# TB_Power_supply_pcb.net
KiCad netlist of a schematic drawn in Altium Designer
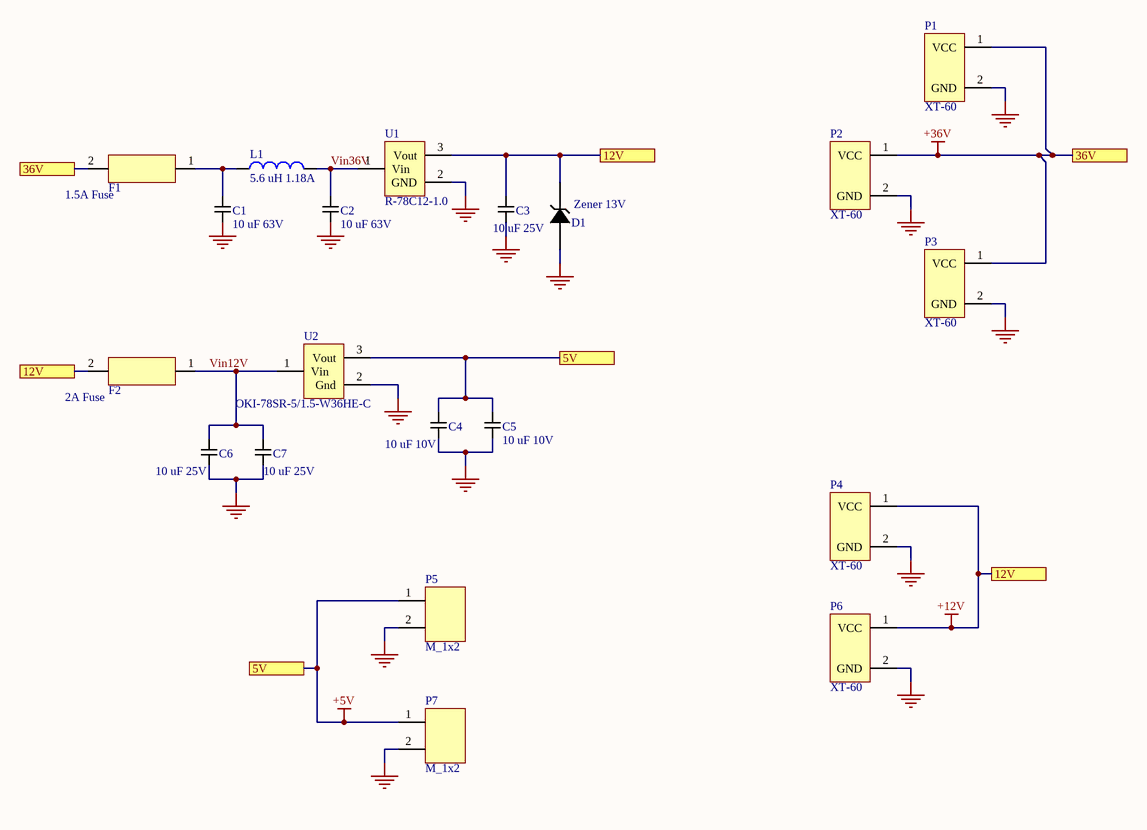
[diagram p0: TB Power supply pcb.SchDoc]

(export (version "E")
  (design (tool "Eeschema 10.0.6"))
  (components
    (comp (ref "C1")
      (value "10 uF 63V")
      (footprint "C_smd_3225")
      (fields (field (name "Comment") "SMD"))
      (libsource (lib "FF_component_lib") (part "C_SMD_3225"))
    )
    (comp (ref "C2")
      (value "10 uF 63V")
      (footprint "C_smd_3225")
      (fields (field (name "Comment") "SMD"))
      (libsource (lib "FF_component_lib") (part "C_SMD_3225"))
    )
    (comp (ref "C3")
      (value "10 uF 25V")
      (footprint "C_SMD_0805_pcb")
      (fields (field (name "Comment") "SMD"))
      (libsource (lib "FF_component_lib") (part "C_SMD_0805"))
    )
    (comp (ref "C4")
      (value "10 uF 10V")
      (footprint "C_SMD_0805_pcb")
      (fields (field (name "Comment") "SMD"))
      (libsource (lib "FF_component_lib") (part "C_SMD_0805"))
    )
    (comp (ref "C5")
      (value "10 uF 10V")
      (footprint "C_SMD_0805_pcb")
      (fields (field (name "Comment") "SMD"))
      (libsource (lib "FF_component_lib") (part "C_SMD_0805"))
    )
    (comp (ref "C6")
      (value "10 uF 25V")
      (footprint "C_SMD_0805_pcb")
      (fields (field (name "Comment") "SMD"))
      (libsource (lib "FF_component_lib") (part "C_SMD_0805"))
    )
    (comp (ref "C7")
      (value "10 uF 25V")
      (footprint "C_SMD_0805_pcb")
      (fields (field (name "Comment") "SMD"))
      (libsource (lib "FF_component_lib") (part "C_SMD_0805"))
    )
    (comp (ref "D1")
      (value "Zener 13V")
      (footprint "D_ZENER_12V_smd")
      (fields (field (name "Comment") "D_ZENER_smd_13V"))
      (libsource (lib "FF_component_lib") (part "D_ZENER_smd_13V"))
    )
    (comp (ref "F1")
      (value "1.5A Fuse")
      (footprint "fuse_holder_3A")
      (description "(22.352mm x6.858mm)")
      (fields (field (name "Comment") "Fuse-holder-3A"))
      (libsource (lib "FF_component_lib") (part "Fuse-holder-3A"))
    )
    (comp (ref "F2")
      (value "2A Fuse")
      (footprint "fuse_holder_3A")
      (description "(22.352mm x6.858mm)")
      (fields (field (name "Comment") "Fuse-holder-3A"))
      (libsource (lib "FF_component_lib") (part "Fuse-holder-3A"))
    )
    (comp (ref "L1")
      (value "5.6 uH 1.18A")
      (footprint "L_1.18A_4532")
      (fields (field (name "Comment") "L_1.18A_4532"))
      (libsource (lib "FF_component_lib") (part "L_1.18A_4532"))
    )
    (comp (ref "P1") (value "XT-60") (footprint "XT-60") (libsource (lib "FF_component_lib") (part "XT-60")))
    (comp (ref "P2") (value "XT-60") (footprint "XT-60") (libsource (lib "FF_component_lib") (part "XT-60")))
    (comp (ref "P3") (value "XT-60") (footprint "XT-60") (libsource (lib "FF_component_lib") (part "XT-60")))
    (comp (ref "P4") (value "XT-60") (footprint "XT-60") (libsource (lib "FF_component_lib") (part "XT-60")))
    (comp (ref "P5")
      (value "M_1x2")
      (footprint "PIN_HEADER_M_1x2")
      (libsource (lib "FF_component_lib") (part "PIN_HEADER_M_1x2"))
    )
    (comp (ref "P6") (value "XT-60") (footprint "XT-60") (libsource (lib "FF_component_lib") (part "XT-60")))
    (comp (ref "P7")
      (value "M_1x2")
      (footprint "PIN_HEADER_M_1x2")
      (libsource (lib "FF_component_lib") (part "PIN_HEADER_M_1x2"))
    )
    (comp (ref "U1")
      (value "R-78C12-1.0")
      (footprint "R-78C12-1.0")
      (description "Wide input - 12V out buck")
      (libsource (lib "FF_component_lib") (part "R-78C12-1.0"))
    )
    (comp (ref "U2")
      (value "OKI-78SR-5/1.5-W36HE-C")
      (footprint "OKI-78SR-5/1.5-W36HE-C")
      (description "12V-5V buck")
      (libsource (lib "FF_component_lib") (part "OKI-78SR-5/1.5-W36HE-C"))
    )
  )
  (nets
    (net (code "1") (name "+5V") (class "Default")
      (node (ref "C4") (pin "1") (pinfunction "1_1") (pintype "passive"))
      (node (ref "C5") (pin "1") (pinfunction "1_1") (pintype "passive"))
      (node (ref "P5") (pin "1") (pinfunction "1_1") (pintype "passive"))
      (node (ref "P7") (pin "1") (pinfunction "1_1") (pintype "passive"))
      (node (ref "U2") (pin "3") (pinfunction "Vout_3") (pintype "passive"))
    )
    (net (code "2") (name "+12V") (class "Default")
      (node (ref "C3") (pin "1") (pinfunction "1_1") (pintype "passive"))
      (node (ref "D1") (pin "2") (pinfunction "2_2") (pintype "passive"))
      (node (ref "F2") (pin "2") (pinfunction "VIN_2") (pintype "passive"))
      (node (ref "P4") (pin "1") (pinfunction "VCC_1") (pintype "passive"))
      (node (ref "P6") (pin "1") (pinfunction "VCC_1") (pintype "passive"))
      (node (ref "U1") (pin "3") (pinfunction "Vout_3") (pintype "passive"))
    )
    (net (code "3") (name "+36V") (class "Default")
      (node (ref "F1") (pin "2") (pinfunction "VIN_2") (pintype "passive"))
      (node (ref "P1") (pin "1") (pinfunction "VCC_1") (pintype "passive"))
      (node (ref "P2") (pin "1") (pinfunction "VCC_1") (pintype "passive"))
      (node (ref "P3") (pin "1") (pinfunction "VCC_1") (pintype "passive"))
    )
    (net (code "4") (name "/Vin12V") (class "Default")
      (node (ref "C6") (pin "1") (pinfunction "1_1") (pintype "passive"))
      (node (ref "C7") (pin "1") (pinfunction "1_1") (pintype "passive"))
      (node (ref "F2") (pin "1") (pinfunction "VIN_1") (pintype "passive"))
      (node (ref "U2") (pin "1") (pinfunction "Vin_1") (pintype "passive"))
    )
    (net (code "5") (name "/Vin36V") (class "Default")
      (node (ref "C2") (pin "1") (pinfunction "1_1") (pintype "passive"))
      (node (ref "L1") (pin "2") (pinfunction "2_2") (pintype "passive"))
      (node (ref "U1") (pin "1") (pinfunction "Vin_1") (pintype "passive"))
    )
    (net (code "6") (name "GND") (class "Default")
      (node (ref "C1") (pin "2") (pinfunction "2_2") (pintype "passive"))
      (node (ref "C2") (pin "2") (pinfunction "2_2") (pintype "passive"))
      (node (ref "C3") (pin "2") (pinfunction "2_2") (pintype "passive"))
      (node (ref "C4") (pin "2") (pinfunction "2_2") (pintype "passive"))
      (node (ref "C5") (pin "2") (pinfunction "2_2") (pintype "passive"))
      (node (ref "C6") (pin "2") (pinfunction "2_2") (pintype "passive"))
      (node (ref "C7") (pin "2") (pinfunction "2_2") (pintype "passive"))
      (node (ref "D1") (pin "1") (pinfunction "56_1") (pintype "passive"))
      (node (ref "P1") (pin "2") (pinfunction "GND_2") (pintype "passive"))
      (node (ref "P2") (pin "2") (pinfunction "GND_2") (pintype "passive"))
      (node (ref "P3") (pin "2") (pinfunction "GND_2") (pintype "passive"))
      (node (ref "P4") (pin "2") (pinfunction "GND_2") (pintype "passive"))
      (node (ref "P5") (pin "2") (pinfunction "2_2") (pintype "passive"))
      (node (ref "P6") (pin "2") (pinfunction "GND_2") (pintype "passive"))
      (node (ref "P7") (pin "2") (pinfunction "2_2") (pintype "passive"))
      (node (ref "U1") (pin "2") (pinfunction "GND_2") (pintype "passive"))
      (node (ref "U2") (pin "2") (pinfunction "Gnd_2") (pintype "passive"))
    )
    (net (code "7") (name "Net-(C1-Pad1)") (class "Default")
      (node (ref "C1") (pin "1") (pinfunction "1_1") (pintype "passive"))
      (node (ref "F1") (pin "1") (pinfunction "VIN_1") (pintype "passive"))
      (node (ref "L1") (pin "1") (pinfunction "1_1") (pintype "passive"))
    )
  )
)
